# LIDO-HW_200_SecurityAndTemperature.net
KiCad netlist of a schematic drawn in Altium Designer
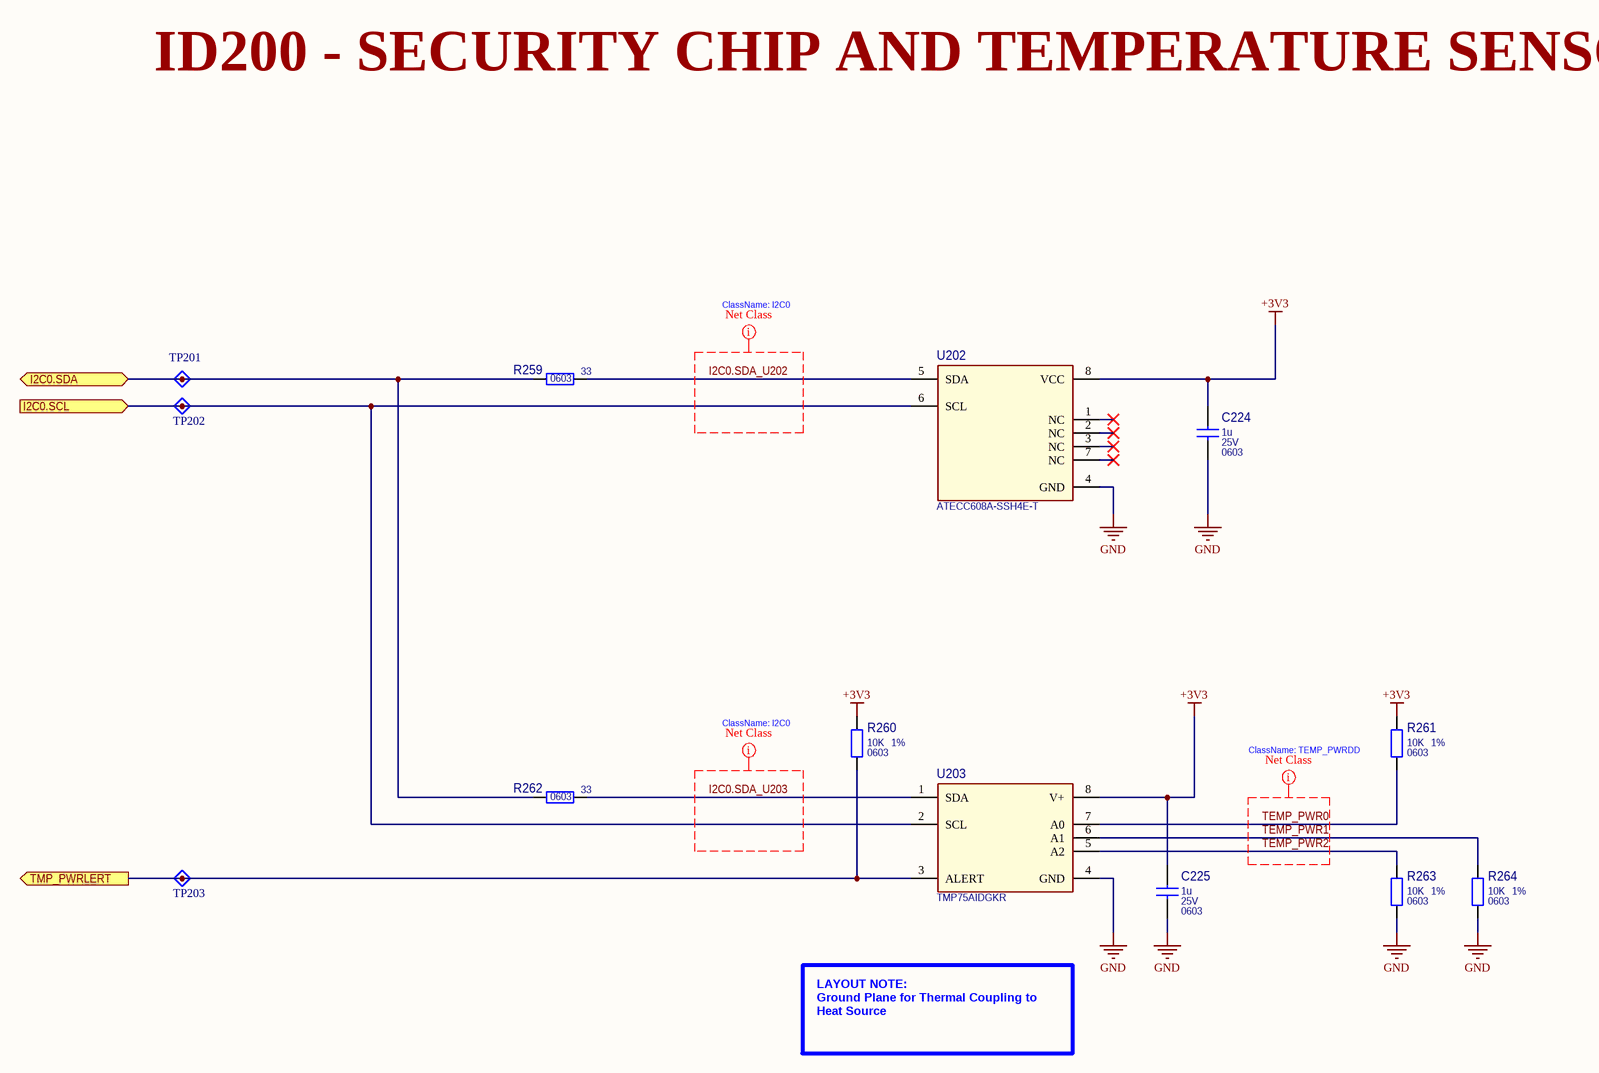
[diagram p0: LIDO-HW.200.SecurityAndTemperature.SchDoc]

(export (version "E")
  (design (tool "Eeschema 10.0.6"))
  (components
    (comp (ref "C224")
      (value "1u")
      (footprint "CAP_0603_1608X90-N_MURATA_A")
      (description "CAP CER 1UF 25V X7R 0603")
      (fields
        (field (name "MANUFACTURER PART NUMBER") "CGA3E1X7R1E105M080AE")
        (field (name "MANUFACTURER") "TDK Corporation")
        (field (name "PART VALUE 2") "25V")
        (field (name "PART PACKAGE") "0603")
      )
      (libsource (lib "DB_Library") (part "Ceramic"))
    )
    (comp (ref "C225")
      (value "1u")
      (footprint "CAP_0603_1608X90-N_MURATA_A")
      (description "CAP CER 1UF 25V X7R 0603")
      (fields
        (field (name "MANUFACTURER PART NUMBER") "CGA3E1X7R1E105M080AE")
        (field (name "MANUFACTURER") "TDK Corporation")
        (field (name "PART VALUE 2") "25V")
        (field (name "PART PACKAGE") "0603")
      )
      (libsource (lib "DB_Library") (part "Ceramic"))
    )
    (comp (ref "R259")
      (value "33")
      (footprint "RES_0603_1608X60-N_YAGEO_A")
      (description "RES 33 OHM 5% 1/10W 0603")
      (fields
        (field (name "MANUFACTURER PART NUMBER") "RC0603JR-0733RL")
        (field (name "MANUFACTURER") "YAGEO")
        (field (name "PART PACKAGE") "0603")
      )
      (libsource (lib "DB_Library") (part "Resistor"))
    )
    (comp (ref "R260")
      (value "10K")
      (footprint "RES_0603_1608X60-N_YAGEO_A")
      (description "RES 10K OHM 1% 1/10W 0603")
      (fields
        (field (name "MANUFACTURER PART NUMBER") "RC0603FR-0710KL")
        (field (name "MANUFACTURER") "YAGEO")
        (field (name "PART VALUE 2") "1%")
        (field (name "PART PACKAGE") "0603")
      )
      (libsource (lib "") (part "Resistor_1"))
    )
    (comp (ref "R261")
      (value "10K")
      (footprint "RES_0603_1608X60-N_YAGEO_A")
      (description "RES 10K OHM 1% 1/10W 0603")
      (fields
        (field (name "MANUFACTURER PART NUMBER") "RC0603FR-0710KL")
        (field (name "MANUFACTURER") "YAGEO")
        (field (name "PART VALUE 2") "1%")
        (field (name "PART PACKAGE") "0603")
      )
      (libsource (lib "") (part "Resistor_1"))
    )
    (comp (ref "R262")
      (value "33")
      (footprint "RES_0603_1608X60-N_YAGEO_A")
      (description "RES 33 OHM 5% 1/10W 0603")
      (fields
        (field (name "MANUFACTURER PART NUMBER") "RC0603JR-0733RL")
        (field (name "MANUFACTURER") "YAGEO")
        (field (name "PART PACKAGE") "0603")
      )
      (libsource (lib "DB_Library") (part "Resistor"))
    )
    (comp (ref "R263")
      (value "10K")
      (footprint "RES_0603_1608X60-N_YAGEO_A")
      (description "RES 10K OHM 1% 1/10W 0603")
      (fields
        (field (name "MANUFACTURER PART NUMBER") "RC0603FR-0710KL")
        (field (name "MANUFACTURER") "YAGEO")
        (field (name "PART VALUE 2") "1%")
        (field (name "PART PACKAGE") "0603")
      )
      (libsource (lib "") (part "Resistor_1"))
    )
    (comp (ref "R264")
      (value "10K")
      (footprint "RES_0603_1608X60-N_YAGEO_A")
      (description "RES 10K OHM 1% 1/10W 0603")
      (fields
        (field (name "MANUFACTURER PART NUMBER") "RC0603FR-0710KL")
        (field (name "MANUFACTURER") "YAGEO")
        (field (name "PART VALUE 2") "1%")
        (field (name "PART PACKAGE") "0603")
      )
      (libsource (lib "") (part "Resistor_1"))
    )
    (comp (ref "TP201")
      (value "TestPoint_A")
      (footprint "TESTPOINT_1D_A")
      (description "Pad Diamater 1mm")
      (fields (field (name "PART") "Test Point 1D A") (field (name "OBSOLETE PART") "False"))
      (libsource (lib "DB_Library") (part "TestPoint_A"))
    )
    (comp (ref "TP202")
      (value "TestPoint_A")
      (footprint "TESTPOINT_1D_A")
      (description "Pad Diamater 1mm")
      (fields (field (name "PART") "Test Point 1D A") (field (name "OBSOLETE PART") "False"))
      (libsource (lib "DB_Library") (part "TestPoint_A"))
    )
    (comp (ref "TP203")
      (value "TestPoint_A")
      (footprint "TESTPOINT_1D_A")
      (description "Pad Diamater 1mm")
      (fields (field (name "PART") "Test Point 1D A") (field (name "OBSOLETE PART") "False"))
      (libsource (lib "DB_Library") (part "TestPoint_A"))
    )
    (comp (ref "U202")
      (value "ATECC608A-SSH4E-T")
      (footprint "SOIC8P127_490X600X175L84X41-N_TI_A")
      (description "IC AUTHENTICATION CHIP 8SOIC")
      (fields
        (field (name "MANUFACTURER") "Microchip Technology")
        (field (name "OBSOLETE PART") "False")
        (field (name "DESIGNER") "Dekimo")
        (field (name "REVIEWED") "Dekimo_30-06-2020")
      )
      (libsource (lib "DB_Library") (part "ATECC608A-SSHDA_A"))
    )
    (comp (ref "U203")
      (value "TMP75AIDGKR")
      (footprint "VSSOP8P65_300X490X110L55X32-N_TI_A")
      (description "Temperature Sensor Digital, Local -40°C ~ 125°C 11 b 8-VSSOP")
      (fields
        (field (name "MANUFACTURER") "Texas Instruments")
        (field (name "OBSOLETE PART") "False")
        (field (name "DESIGNER") "Matt Drazenovich")
        (field (name "REVIEWED") "Dekimo_07-07-2020")
      )
      (libsource (lib "DB_Library") (part "TMP75AIDGKR_A"))
    )
  )
  (nets
    (net (code "1") (name "+3V3") (class "Default")
      (node (ref "C224") (pin "1") (pinfunction "1_1") (pintype "passive"))
      (node (ref "C225") (pin "1") (pinfunction "1_1") (pintype "passive"))
      (node (ref "R260") (pin "2") (pinfunction "2_2") (pintype "passive"))
      (node (ref "R261") (pin "2") (pinfunction "2_2") (pintype "passive"))
      (node (ref "U202") (pin "8") (pinfunction "VCC_8") (pintype "passive"))
      (node (ref "U203") (pin "8") (pinfunction "V+_8") (pintype "passive"))
    )
    (net (code "2") (name "/I2C0.SCL") (class "Default")
      (node (ref "TP202") (pin "1") (pinfunction "TP_1") (pintype "passive"))
      (node (ref "U202") (pin "6") (pinfunction "SCL_6") (pintype "passive"))
      (node (ref "U203") (pin "2") (pinfunction "SCL_2") (pintype "passive"))
    )
    (net (code "3") (name "/I2C0.SDA") (class "Default")
      (node (ref "R259") (pin "1") (pinfunction "1_1") (pintype "passive"))
      (node (ref "R262") (pin "1") (pinfunction "1_1") (pintype "passive"))
      (node (ref "TP201") (pin "1") (pinfunction "TP_1") (pintype "passive"))
    )
    (net (code "4") (name "/I2C0.SDA_U202") (class "Default")
      (node (ref "R259") (pin "2") (pinfunction "2_2") (pintype "passive"))
      (node (ref "U202") (pin "5") (pinfunction "SDA_5") (pintype "passive"))
    )
    (net (code "5") (name "/I2C0.SDA_U203") (class "Default")
      (node (ref "R262") (pin "2") (pinfunction "2_2") (pintype "passive"))
      (node (ref "U203") (pin "1") (pinfunction "SDA_1") (pintype "passive"))
    )
    (net (code "6") (name "/TEMP_PWR0") (class "Default")
      (node (ref "R261") (pin "1") (pinfunction "1_1") (pintype "passive"))
      (node (ref "U203") (pin "7") (pinfunction "A0_7") (pintype "passive"))
    )
    (net (code "7") (name "/TEMP_PWR1") (class "Default")
      (node (ref "R264") (pin "2") (pinfunction "2_2") (pintype "passive"))
      (node (ref "U203") (pin "6") (pinfunction "A1_6") (pintype "passive"))
    )
    (net (code "8") (name "/TEMP_PWR2") (class "Default")
      (node (ref "R263") (pin "2") (pinfunction "2_2") (pintype "passive"))
      (node (ref "U203") (pin "5") (pinfunction "A2_5") (pintype "passive"))
    )
    (net (code "9") (name "/TMP_PWRLERT") (class "Default")
      (node (ref "R260") (pin "1") (pinfunction "1_1") (pintype "passive"))
      (node (ref "TP203") (pin "1") (pinfunction "TP_1") (pintype "passive"))
      (node (ref "U203") (pin "3") (pinfunction "ALERT_3") (pintype "passive"))
    )
    (net (code "10") (name "GND") (class "Default")
      (node (ref "C224") (pin "2") (pinfunction "2_2") (pintype "passive"))
      (node (ref "C225") (pin "2") (pinfunction "2_2") (pintype "passive"))
      (node (ref "R263") (pin "1") (pinfunction "1_1") (pintype "passive"))
      (node (ref "R264") (pin "1") (pinfunction "1_1") (pintype "passive"))
      (node (ref "U202") (pin "4") (pinfunction "GND_4") (pintype "passive"))
      (node (ref "U203") (pin "4") (pinfunction "GND_4") (pintype "passive"))
    )
    (net (code "11") (name "unconnected-(U202-NC-Pad1)") (class "Default")
      (node (ref "U202") (pin "1") (pinfunction "NC_1") (pintype "passive+no_connect"))
    )
    (net (code "12") (name "unconnected-(U202-NC-Pad2)") (class "Default")
      (node (ref "U202") (pin "2") (pinfunction "NC_2") (pintype "passive+no_connect"))
    )
    (net (code "13") (name "unconnected-(U202-NC-Pad3)") (class "Default")
      (node (ref "U202") (pin "3") (pinfunction "NC_3") (pintype "passive+no_connect"))
    )
    (net (code "14") (name "unconnected-(U202-NC-Pad7)") (class "Default")
      (node (ref "U202") (pin "7") (pinfunction "NC_7") (pintype "passive+no_connect"))
    )
  )
)
